# power.net
KiCad netlist of a schematic drawn in Altium Designer
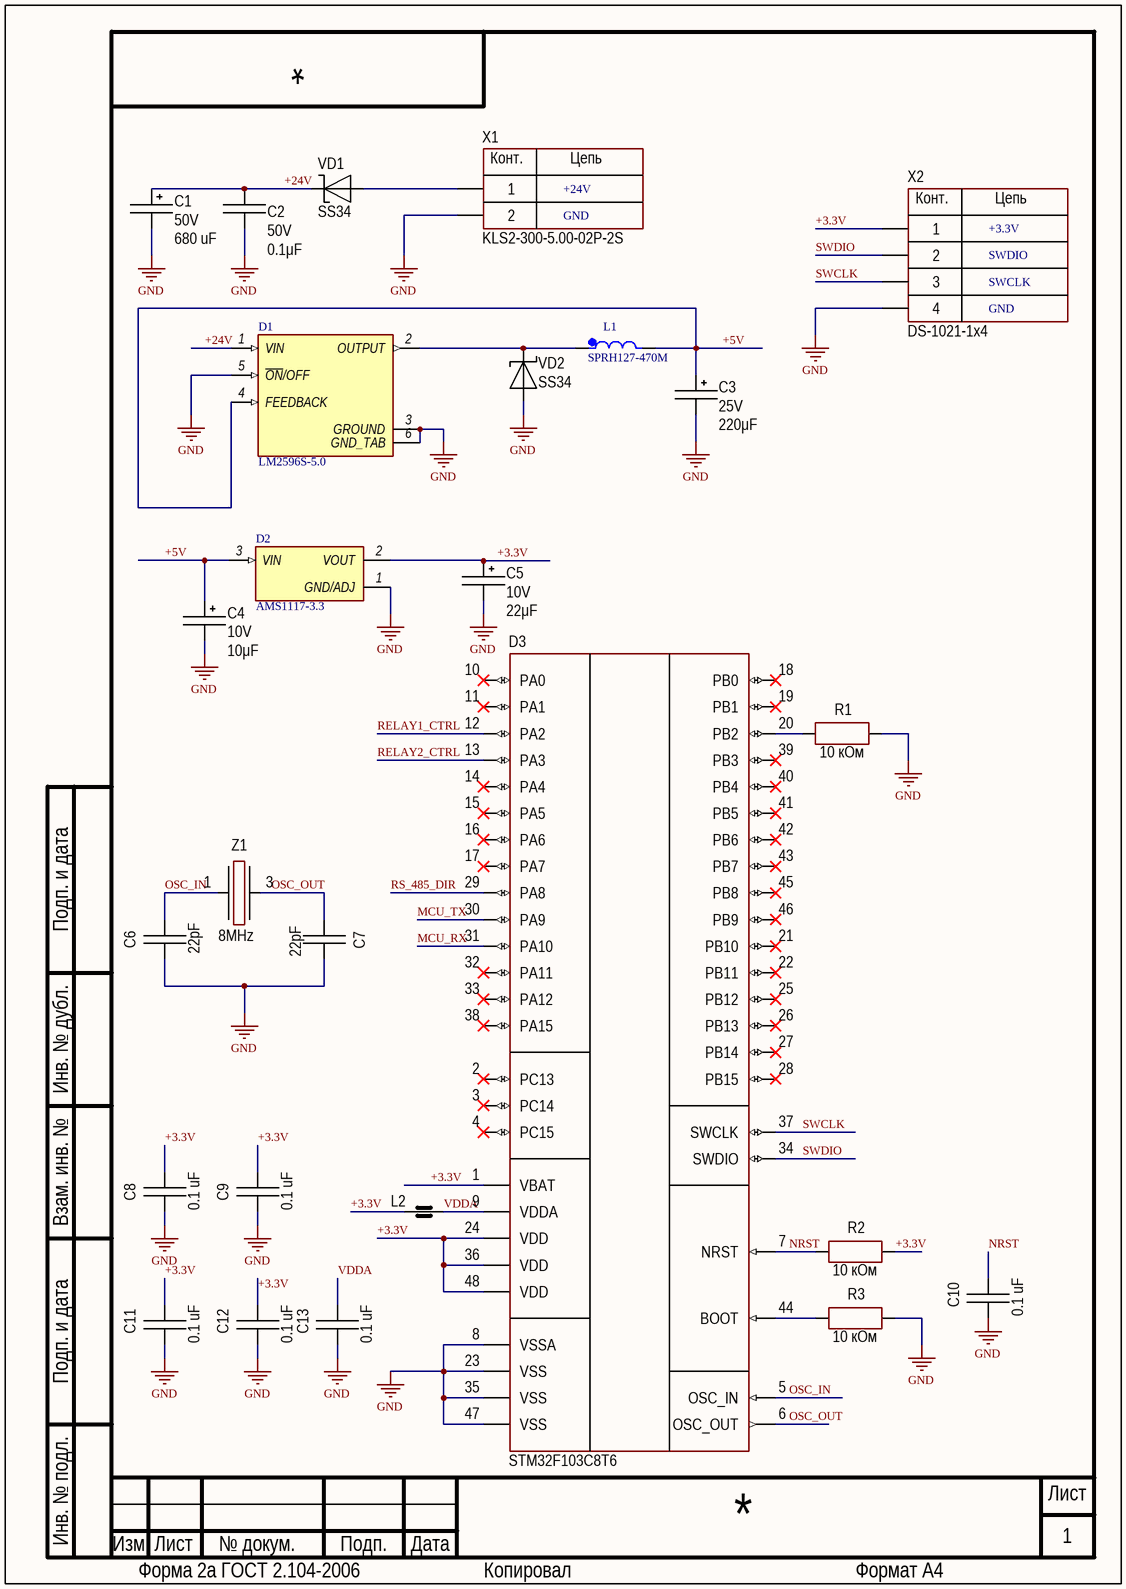
[diagram p0: power.SchDoc]

(export (version "E")
  (design (tool "Eeschema 10.0.6"))
  (components
    (comp (ref "C1")
      (value "680 uF")
      (footprint "standard-case:CAP: D13C5H20")
      (fields
        (field (name "MANUFACTURER") "Wurth")
        (field (name "PARTNUMBER") "860080475013")
        (field (name "VALUEMANUFACTURERPARTNUMBER") "Aluminium capacitor, 680 uF, 50V, ±20%, 54mOhm, 14x10x5 mm, -55...+105°C")
        (field (name "VOLTAGE") "50V")
      )
      (libsource (lib "capacitor") (part "Aluminium"))
    )
    (comp (ref "C2")
      (value "0.1μF")
      (footprint "standard-case:CAP: 0603")
      (fields
        (field (name "MANUFACTURER") "Yageo")
        (field (name "PARTNUMBER") "CC0603KRX7R7BB104")
        (field (name "VALUEMANUFACTURERPARTNUMBER") "Ceramic capacitor, 0.1μF, X7R, ±10%, 50V, 0603, -55...+125°C")
        (field (name "VOLTAGE") "50V")
      )
      (libsource (lib "capacitor") (part "Ceramic_0603"))
    )
    (comp (ref "C3")
      (value "220μF")
      (footprint "standard-case:CAP: D8C3.5H12")
      (fields
        (field (name "MANUFACTURER") "Wurth")
        (field (name "PARTNUMBER") "860080475013")
        (field (name "VALUEMANUFACTURERPARTNUMBER") "Aluminium capacitor, 220μF, 25V, ±20%, 54mOhm, 14x10x5 mm, -55...+105°C")
        (field (name "VOLTAGE") "25V")
      )
      (libsource (lib "capacitor") (part "Aluminium"))
    )
    (comp (ref "C4")
      (value "10μF")
      (footprint "standard-case:CAP: TANTAL-A")
      (fields
        (field (name "MANUFACTURER") "AVX")
        (field (name "PARTNUMBER") "F930J107KAAAJ6")
        (field (name "VALUEMANUFACTURERPARTNUMBER") "Tantalum capacitor, 10μF, 10V, ±10%, 2Ohm, case A (3216), -55...+125°C")
        (field (name "VOLTAGE") "10V")
      )
      (libsource (lib "capacitor") (part "Tantal_A"))
    )
    (comp (ref "C5")
      (value "22μF")
      (footprint "standard-case:CAP: TANTAL-B")
      (fields
        (field (name "MANUFACTURER") "AVX")
        (field (name "PARTNUMBER") "F930J227KBA")
        (field (name "VALUEMANUFACTURERPARTNUMBER") "Tantalum capacitor, 22μF, 10V, ±10%, 1.2Ohm, case B (3528), -55...+125°C")
        (field (name "VOLTAGE") "10V")
      )
      (libsource (lib "capacitor") (part "Tantal_B"))
    )
    (comp (ref "C6")
      (value "22pF")
      (footprint "standard:CH0603C")
      (libsource (lib "Discrete") (part "Capacitor"))
    )
    (comp (ref "C7")
      (value "22pF")
      (footprint "standard:CH0603C")
      (libsource (lib "Discrete") (part "Capacitor"))
    )
    (comp (ref "C8")
      (value "0.1 uF")
      (footprint "standard:CH0603C")
      (libsource (lib "Discrete") (part "Capacitor"))
    )
    (comp (ref "C9")
      (value "0.1 uF")
      (footprint "standard:CH0603C")
      (libsource (lib "Discrete") (part "Capacitor"))
    )
    (comp (ref "C10")
      (value "0.1 uF")
      (footprint "standard:CH0603C")
      (libsource (lib "Discrete") (part "Capacitor"))
    )
    (comp (ref "C11")
      (value "0.1 uF")
      (footprint "standard:CH0603C")
      (libsource (lib "Discrete") (part "Capacitor"))
    )
    (comp (ref "C12")
      (value "0.1 uF")
      (footprint "standard:CH0603C")
      (libsource (lib "Discrete") (part "Capacitor"))
    )
    (comp (ref "C13")
      (value "0.1 uF")
      (footprint "standard:CH0603C")
      (libsource (lib "Discrete") (part "Capacitor"))
    )
    (comp (ref "D1")
      (value "LM2596S-5.0")
      (footprint "TO170P1524X483-6N")
      (description "SIMPLE SWITCHERÂ® 4.5V to 40V, 3A Low Component Count Step-Down Regulator")
      (fields (field (name "MF") "Texas Instruments") (field (name "MP") "LM2596S-5.0/NOPB"))
      (libsource (lib "LM2596S-5.0") (part "LM2596S-5.0"))
    )
    (comp (ref "D2")
      (value "AMS1117-3.3")
      (footprint "SOT229P700X180-4N")
      (description "Sot223/Pkg 1-Amp 3.3-Volt Low Drop Out Voltage Regulatator")
      (fields (field (name "MF") "Advanced Monolithic Systems"))
      (libsource (lib "AMS1117-3.3") (part "AMS1117-3.3"))
    )
    (comp (ref "D3")
      (value "STM32F103C8T6")
      (footprint "standard:48-LQFP")
      (description "Cortex-M3")
      (fields (field (name "MANUFACTURER") "ST Microelectronics"))
      (libsource (lib "Digital") (part "STM32F103C8T6"))
    )
    (comp (ref "L1")
      (value "SPRH127-470M")
      (footprint "IND_SPRH127-470M")
      (fields (field (name "MF") "{'manufacturer': u'CODACA'}"))
      (libsource (lib "SPRH127-470M") (part "SPRH127-470M"))
    )
    (comp (ref "L2") (value "*") (footprint "standard:CH0603R") (libsource (lib "Discrete") (part "Bead")))
    (comp (ref "R1")
      (value "10 кОм")
      (footprint "standard:CH0603R")
      (libsource (lib "Discrete") (part "Resistor"))
    )
    (comp (ref "R2")
      (value "10 кОм")
      (footprint "standard:CH0603R")
      (libsource (lib "Discrete") (part "Resistor"))
    )
    (comp (ref "R3")
      (value "10 кОм")
      (footprint "standard:CH0603R")
      (libsource (lib "Discrete") (part "Resistor"))
    )
    (comp (ref "VD1")
      (value "SS34")
      (footprint "standard:SMC")
      (libsource (lib "Diods") (part "Diod Schottky"))
    )
    (comp (ref "VD2")
      (value "SS34")
      (footprint "standard:SMC")
      (libsource (lib "Diods") (part "Diod Schottky"))
    )
    (comp (ref "X1")
      (value "KLS2-300-5.00-02P-2S")
      (footprint "custom:CON: 300-02P-5.0")
      (libsource (lib "Connectors") (part "2-Connector"))
    )
    (comp (ref "X2")
      (value "DS-1021-1x4")
      (footprint "custom:CON: PLS-4")
      (libsource (lib "Connectors") (part "4-Connector"))
    )
    (comp (ref "Z1")
      (value "8MHz")
      (footprint "custom:OSC: 2520")
      (libsource (lib "Discrete") (part "Oscillator"))
    )
  )
  (nets
    (net (code "1") (name "/+3.3V") (class "Default")
      (node (ref "C11") (pin "2") (pinfunction "2_2") (pintype "power_in"))
      (node (ref "C12") (pin "2") (pinfunction "2_2") (pintype "power_in"))
      (node (ref "C5") (pin "1") (pinfunction "1_1") (pintype "passive"))
      (node (ref "C8") (pin "2") (pinfunction "2_2") (pintype "power_in"))
      (node (ref "C9") (pin "2") (pinfunction "2_2") (pintype "power_in"))
      (node (ref "D2") (pin "2") (pinfunction "VOUT_2") (pintype "power_in"))
      (node (ref "D3") (pin "1") (pinfunction "VBAT_1") (pintype "power_in"))
      (node (ref "D3") (pin "24") (pinfunction "VDD_24") (pintype "power_in"))
      (node (ref "D3") (pin "36") (pinfunction "VDD_36") (pintype "power_in"))
      (node (ref "D3") (pin "48") (pinfunction "VDD_48") (pintype "power_in"))
      (node (ref "L2") (pin "1") (pinfunction "1_1") (pintype "passive"))
      (node (ref "R2") (pin "2") (pinfunction "2_2") (pintype "passive"))
      (node (ref "X2") (pin "1") (pinfunction "1_1") (pintype "passive"))
    )
    (net (code "2") (name "/+5V") (class "Default")
      (node (ref "C3") (pin "1") (pinfunction "1_1") (pintype "passive"))
      (node (ref "C4") (pin "1") (pinfunction "1_1") (pintype "passive"))
      (node (ref "D1") (pin "4") (pinfunction "FEEDBACK_4") (pintype "input"))
      (node (ref "D2") (pin "3") (pinfunction "VIN_3") (pintype "input"))
      (node (ref "L1") (pin "2") (pinfunction "2_2") (pintype "passive"))
    )
    (net (code "3") (name "/+24V") (class "Default")
      (node (ref "C1") (pin "1") (pinfunction "1_1") (pintype "passive"))
      (node (ref "C2") (pin "2") (pinfunction "2_2") (pintype "passive"))
      (node (ref "D1") (pin "1") (pinfunction "VIN_1") (pintype "input"))
      (node (ref "VD1") (pin "2") (pinfunction "2_2") (pintype "passive"))
    )
    (net (code "4") (name "/MCU_RX") (class "Default")
      (node (ref "D3") (pin "31") (pinfunction "PA10_31") (pintype "bidirectional"))
    )
    (net (code "5") (name "/MCU_TX") (class "Default")
      (node (ref "D3") (pin "30") (pinfunction "PA9_30") (pintype "bidirectional"))
    )
    (net (code "6") (name "/NRST") (class "Default")
      (node (ref "C10") (pin "2") (pinfunction "2_2") (pintype "power_in"))
      (node (ref "D3") (pin "7") (pinfunction "NRST_7") (pintype "input"))
      (node (ref "R2") (pin "1") (pinfunction "1_1") (pintype "passive"))
    )
    (net (code "7") (name "/OSC_IN") (class "Default")
      (node (ref "C6") (pin "2") (pinfunction "2_2") (pintype "power_in"))
      (node (ref "D3") (pin "5") (pinfunction "OSC_IN_5") (pintype "input"))
      (node (ref "Z1") (pin "1") (pinfunction "1_1") (pintype "passive"))
    )
    (net (code "8") (name "/OSC_OUT") (class "Default")
      (node (ref "C7") (pin "1") (pinfunction "1_1") (pintype "power_in"))
      (node (ref "D3") (pin "6") (pinfunction "OSC_OUT_6") (pintype "output"))
      (node (ref "Z1") (pin "3") (pinfunction "3_3") (pintype "passive"))
    )
    (net (code "9") (name "/RELAY1_CTRL") (class "Default")
      (node (ref "D3") (pin "12") (pinfunction "PA2_12") (pintype "bidirectional"))
    )
    (net (code "10") (name "/RELAY2_CTRL") (class "Default")
      (node (ref "D3") (pin "13") (pinfunction "PA3_13") (pintype "bidirectional"))
    )
    (net (code "11") (name "/RS_485_DIR") (class "Default")
      (node (ref "D3") (pin "29") (pinfunction "PA8_29") (pintype "bidirectional"))
    )
    (net (code "12") (name "/SWCLK") (class "Default")
      (node (ref "D3") (pin "37") (pinfunction "SWCLK_37") (pintype "bidirectional"))
      (node (ref "X2") (pin "3") (pinfunction "3_3") (pintype "power_in"))
    )
    (net (code "13") (name "/SWDIO") (class "Default")
      (node (ref "D3") (pin "34") (pinfunction "SWDIO_34") (pintype "bidirectional"))
      (node (ref "X2") (pin "2") (pinfunction "2_2") (pintype "passive"))
    )
    (net (code "14") (name "/VDDA") (class "Default")
      (node (ref "C13") (pin "2") (pinfunction "2_2") (pintype "power_in"))
      (node (ref "D3") (pin "9") (pinfunction "VDDA_9") (pintype "power_in"))
      (node (ref "L2") (pin "2") (pinfunction "2_2") (pintype "passive"))
    )
    (net (code "15") (name "GND") (class "Default")
      (node (ref "C1") (pin "2") (pinfunction "2_2") (pintype "passive"))
      (node (ref "C10") (pin "1") (pinfunction "1_1") (pintype "power_in"))
      (node (ref "C11") (pin "1") (pinfunction "1_1") (pintype "power_in"))
      (node (ref "C12") (pin "1") (pinfunction "1_1") (pintype "power_in"))
      (node (ref "C13") (pin "1") (pinfunction "1_1") (pintype "power_in"))
      (node (ref "C2") (pin "1") (pinfunction "1_1") (pintype "passive"))
      (node (ref "C3") (pin "2") (pinfunction "2_2") (pintype "passive"))
      (node (ref "C4") (pin "2") (pinfunction "2_2") (pintype "passive"))
      (node (ref "C5") (pin "2") (pinfunction "2_2") (pintype "passive"))
      (node (ref "C6") (pin "1") (pinfunction "1_1") (pintype "power_in"))
      (node (ref "C7") (pin "2") (pinfunction "2_2") (pintype "power_in"))
      (node (ref "C8") (pin "1") (pinfunction "1_1") (pintype "power_in"))
      (node (ref "C9") (pin "1") (pinfunction "1_1") (pintype "power_in"))
      (node (ref "D1") (pin "3") (pinfunction "GROUND_3") (pintype "power_in"))
      (node (ref "D1") (pin "5") (pinfunction "~{ON}/OFF_5") (pintype "input"))
      (node (ref "D1") (pin "6") (pinfunction "GND_TAB_6") (pintype "power_in"))
      (node (ref "D2") (pin "1") (pinfunction "GND/ADJ_1") (pintype "power_in"))
      (node (ref "D3") (pin "23") (pinfunction "VSS_23") (pintype "power_in"))
      (node (ref "D3") (pin "35") (pinfunction "VSS_35") (pintype "power_in"))
      (node (ref "D3") (pin "47") (pinfunction "VSS_47") (pintype "power_in"))
      (node (ref "D3") (pin "8") (pinfunction "VSSA_8") (pintype "power_in"))
      (node (ref "R1") (pin "2") (pinfunction "2_2") (pintype "passive"))
      (node (ref "R3") (pin "2") (pinfunction "2_2") (pintype "passive"))
      (node (ref "VD2") (pin "1") (pinfunction "1_1") (pintype "passive"))
      (node (ref "X1") (pin "2") (pinfunction "2_2") (pintype "passive"))
      (node (ref "X2") (pin "4") (pinfunction "4_4") (pintype "power_in"))
    )
    (net (code "16") (name "Net-(D1-OUTPUT)") (class "Default")
      (node (ref "D1") (pin "2") (pinfunction "OUTPUT_2") (pintype "output"))
      (node (ref "L1") (pin "1") (pinfunction "1_1") (pintype "passive"))
      (node (ref "VD2") (pin "2") (pinfunction "2_2") (pintype "passive"))
    )
    (net (code "17") (name "Net-(D3-BOOT)") (class "Default")
      (node (ref "D3") (pin "44") (pinfunction "BOOT_44") (pintype "input"))
      (node (ref "R3") (pin "1") (pinfunction "1_1") (pintype "passive"))
    )
    (net (code "18") (name "Net-(D3-PB2)") (class "Default")
      (node (ref "D3") (pin "20") (pinfunction "PB2_20") (pintype "bidirectional"))
      (node (ref "R1") (pin "1") (pinfunction "1_1") (pintype "passive"))
    )
    (net (code "19") (name "Net-(VD1-Pad1)") (class "Default")
      (node (ref "VD1") (pin "1") (pinfunction "1_1") (pintype "passive"))
      (node (ref "X1") (pin "1") (pinfunction "1_1") (pintype "passive"))
    )
    (net (code "20") (name "unconnected-(D3-PA0-Pad10)") (class "Default")
      (node (ref "D3") (pin "10") (pinfunction "PA0_10") (pintype "bidirectional+no_connect"))
    )
    (net (code "21") (name "unconnected-(D3-PA1-Pad11)") (class "Default")
      (node (ref "D3") (pin "11") (pinfunction "PA1_11") (pintype "bidirectional+no_connect"))
    )
    (net (code "22") (name "unconnected-(D3-PA4-Pad14)") (class "Default")
      (node (ref "D3") (pin "14") (pinfunction "PA4_14") (pintype "bidirectional+no_connect"))
    )
    (net (code "23") (name "unconnected-(D3-PA5-Pad15)") (class "Default")
      (node (ref "D3") (pin "15") (pinfunction "PA5_15") (pintype "bidirectional+no_connect"))
    )
    (net (code "24") (name "unconnected-(D3-PA6-Pad16)") (class "Default")
      (node (ref "D3") (pin "16") (pinfunction "PA6_16") (pintype "bidirectional+no_connect"))
    )
    (net (code "25") (name "unconnected-(D3-PA7-Pad17)") (class "Default")
      (node (ref "D3") (pin "17") (pinfunction "PA7_17") (pintype "bidirectional+no_connect"))
    )
    (net (code "26") (name "unconnected-(D3-PA11-Pad32)") (class "Default")
      (node (ref "D3") (pin "32") (pinfunction "PA11_32") (pintype "bidirectional+no_connect"))
    )
    (net (code "27") (name "unconnected-(D3-PA12-Pad33)") (class "Default")
      (node (ref "D3") (pin "33") (pinfunction "PA12_33") (pintype "bidirectional+no_connect"))
    )
    (net (code "28") (name "unconnected-(D3-PA15-Pad38)") (class "Default")
      (node (ref "D3") (pin "38") (pinfunction "PA15_38") (pintype "bidirectional+no_connect"))
    )
    (net (code "29") (name "unconnected-(D3-PB0-Pad18)") (class "Default")
      (node (ref "D3") (pin "18") (pinfunction "PB0_18") (pintype "bidirectional+no_connect"))
    )
    (net (code "30") (name "unconnected-(D3-PB1-Pad19)") (class "Default")
      (node (ref "D3") (pin "19") (pinfunction "PB1_19") (pintype "bidirectional+no_connect"))
    )
    (net (code "31") (name "unconnected-(D3-PB3-Pad39)") (class "Default")
      (node (ref "D3") (pin "39") (pinfunction "PB3_39") (pintype "bidirectional+no_connect"))
    )
    (net (code "32") (name "unconnected-(D3-PB4-Pad40)") (class "Default")
      (node (ref "D3") (pin "40") (pinfunction "PB4_40") (pintype "bidirectional+no_connect"))
    )
    (net (code "33") (name "unconnected-(D3-PB5-Pad41)") (class "Default")
      (node (ref "D3") (pin "41") (pinfunction "PB5_41") (pintype "bidirectional+no_connect"))
    )
    (net (code "34") (name "unconnected-(D3-PB6-Pad42)") (class "Default")
      (node (ref "D3") (pin "42") (pinfunction "PB6_42") (pintype "bidirectional+no_connect"))
    )
    (net (code "35") (name "unconnected-(D3-PB7-Pad43)") (class "Default")
      (node (ref "D3") (pin "43") (pinfunction "PB7_43") (pintype "bidirectional+no_connect"))
    )
    (net (code "36") (name "unconnected-(D3-PB8-Pad45)") (class "Default")
      (node (ref "D3") (pin "45") (pinfunction "PB8_45") (pintype "bidirectional+no_connect"))
    )
    (net (code "37") (name "unconnected-(D3-PB9-Pad46)") (class "Default")
      (node (ref "D3") (pin "46") (pinfunction "PB9_46") (pintype "bidirectional+no_connect"))
    )
    (net (code "38") (name "unconnected-(D3-PB10-Pad21)") (class "Default")
      (node (ref "D3") (pin "21") (pinfunction "PB10_21") (pintype "bidirectional+no_connect"))
    )
    (net (code "39") (name "unconnected-(D3-PB11-Pad22)") (class "Default")
      (node (ref "D3") (pin "22") (pinfunction "PB11_22") (pintype "bidirectional+no_connect"))
    )
    (net (code "40") (name "unconnected-(D3-PB12-Pad25)") (class "Default")
      (node (ref "D3") (pin "25") (pinfunction "PB12_25") (pintype "bidirectional+no_connect"))
    )
    (net (code "41") (name "unconnected-(D3-PB13-Pad26)") (class "Default")
      (node (ref "D3") (pin "26") (pinfunction "PB13_26") (pintype "bidirectional+no_connect"))
    )
    (net (code "42") (name "unconnected-(D3-PB14-Pad27)") (class "Default")
      (node (ref "D3") (pin "27") (pinfunction "PB14_27") (pintype "bidirectional+no_connect"))
    )
    (net (code "43") (name "unconnected-(D3-PB15-Pad28)") (class "Default")
      (node (ref "D3") (pin "28") (pinfunction "PB15_28") (pintype "bidirectional+no_connect"))
    )
    (net (code "44") (name "unconnected-(D3-PC13-Pad2)") (class "Default")
      (node (ref "D3") (pin "2") (pinfunction "PC13_2") (pintype "bidirectional+no_connect"))
    )
    (net (code "45") (name "unconnected-(D3-PC14-Pad3)") (class "Default")
      (node (ref "D3") (pin "3") (pinfunction "PC14_3") (pintype "bidirectional+no_connect"))
    )
    (net (code "46") (name "unconnected-(D3-PC15-Pad4)") (class "Default")
      (node (ref "D3") (pin "4") (pinfunction "PC15_4") (pintype "bidirectional+no_connect"))
    )
  )
)
